# DotSolar.net
KiCad netlist of a schematic drawn in EAGLE
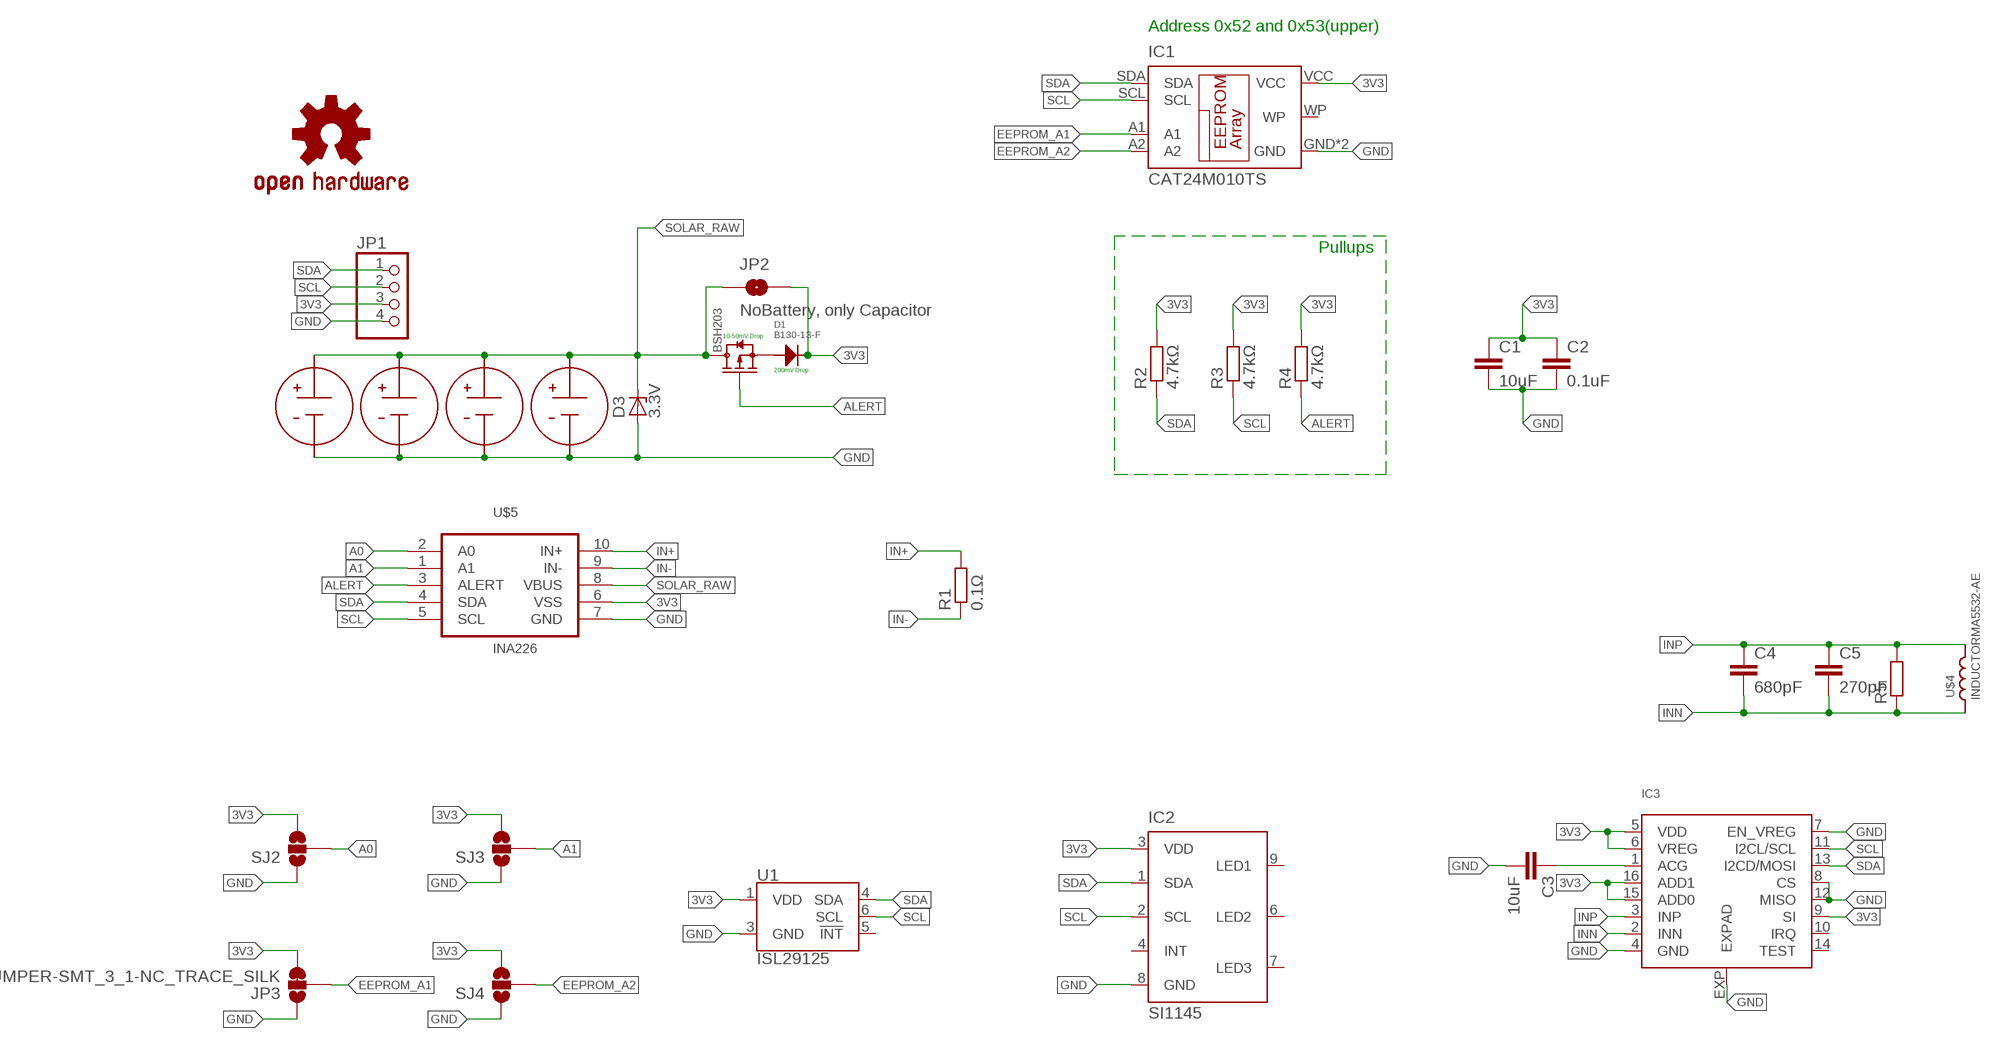
[diagram p0: schematic, sheet 1]

(export (version "E")
  (design (tool "Eeschema 10.0.6"))
  (components
    (comp (ref "C1")
      (value "10uF")
      (footprint "eagle-import:C0603")
      (libsource (lib "eagle-import") (part "C-EUC0603"))
    )
    (comp (ref "C2")
      (value "0.1uF")
      (footprint "eagle-import:C0603")
      (libsource (lib "eagle-import") (part "C-EUC0603"))
    )
    (comp (ref "C3")
      (value "10uF")
      (footprint "eagle-import:C0603")
      (libsource (lib "eagle-import") (part "C-EUC0603"))
    )
    (comp (ref "C4")
      (value "680pF")
      (footprint "eagle-import:C0603")
      (libsource (lib "eagle-import") (part "C-EUC0603"))
    )
    (comp (ref "C5")
      (value "270pF")
      (footprint "eagle-import:C0603")
      (libsource (lib "eagle-import") (part "C-EUC0603"))
    )
    (comp (ref "D1")
      (value "B130-13-F")
      (footprint "eagle-import:B130-13-F")
      (libsource (lib "eagle-import") (part "DIODE_B130-13-F"))
    )
    (comp (ref "D3")
      (value "3.3V")
      (footprint "eagle-import:SMB")
      (libsource (lib "eagle-import") (part "ZENER-DIODESMB"))
    )
    (comp (ref "IC1")
      (value "CAT24M010TS")
      (footprint "eagle-import:TSSOP8")
      (fields (field (name "MF") "On Semiconductor") (field (name "MPN") "24C00T-E/ST"))
      (libsource (lib "eagle-import") (part "CAT24M01TS0"))
    )
    (comp (ref "IC2")
      (value "SI1145")
      (footprint "eagle-import:QFN-10")
      (libsource (lib "eagle-import") (part "SI1145"))
    )
    (comp (ref "IC3")
      (value "AS3935")
      (footprint "eagle-import:16LDMLPQ")
      (libsource (lib "eagle-import") (part "AS3935"))
    )
    (comp (ref "JP1")
      (value "PINHD-1X4")
      (footprint "eagle-import:1X04")
      (libsource (lib "eagle-import") (part "PINHD-1X4"))
    )
    (comp (ref "JP2")
      (value "NoBattery, only Capacitor")
      (footprint "eagle-import:SMT-JUMPER_2_NO_SILK")
      (libsource (lib "eagle-import") (part "JUMPER-SMT_2_NO_SILK"))
    )
    (comp (ref "JP3")
      (value "JUMPER-SMT_3_1-NC_TRACE_SILK")
      (footprint "eagle-import:SMT-JUMPER_3_1-NC_TRACE_SILK")
      (libsource (lib "eagle-import") (part "JUMPER-SMT_3_1-NC_TRACE_SILK"))
    )
    (comp (ref "LOGO1")
      (value "OSHW-LOGOS")
      (footprint "eagle-import:OSHW-LOGO-S")
      (libsource (lib "eagle-import") (part "OSHW-LOGOS"))
    )
    (comp (ref "Q1")
      (value "BSH203")
      (footprint "eagle-import:SOT-23")
      (libsource (lib "eagle-import") (part "BSH203"))
    )
    (comp (ref "R1")
      (value "0.1Ω")
      (footprint "eagle-import:R0603")
      (libsource (lib "eagle-import") (part "R-EU_R0603"))
    )
    (comp (ref "R2")
      (value "4.7kΩ")
      (footprint "eagle-import:R0603")
      (libsource (lib "eagle-import") (part "R-EU_R0603"))
    )
    (comp (ref "R3")
      (value "4.7kΩ")
      (footprint "eagle-import:R0603")
      (libsource (lib "eagle-import") (part "R-EU_R0603"))
    )
    (comp (ref "R4")
      (value "4.7kΩ")
      (footprint "eagle-import:R0603")
      (libsource (lib "eagle-import") (part "R-EU_R0603"))
    )
    (comp (ref "R5")
      (value "R-EU_R0603")
      (footprint "eagle-import:R0603")
      (libsource (lib "eagle-import") (part "R-EU_R0603"))
    )
    (comp (ref "SJ2")
      (value "SOLDERJUMPER_2WAYPASTE2&3")
      (footprint "eagle-import:SJ_3_PASTE2&3")
      (libsource (lib "eagle-import") (part "SOLDERJUMPER_2WAYPASTE2&3"))
    )
    (comp (ref "SJ3")
      (value "SOLDERJUMPER_2WAYPASTE2&3")
      (footprint "eagle-import:SJ_3_PASTE2&3")
      (libsource (lib "eagle-import") (part "SOLDERJUMPER_2WAYPASTE2&3"))
    )
    (comp (ref "SJ4")
      (value "SOLDERJUMPER_2WAYPASTE2&3")
      (footprint "eagle-import:SJ_3_PASTE2&3")
      (libsource (lib "eagle-import") (part "SOLDERJUMPER_2WAYPASTE2&3"))
    )
    (comp (ref "U$1")
      (value "KXOB22-01X8F_EXTENDED_PADS")
      (footprint "eagle-import:KXOB22-01X8F_EXTENDED_PADS")
      (libsource (lib "eagle-import") (part "KXOB22-01X8F_EXTENDED_PADS"))
    )
    (comp (ref "U$2")
      (value "KXOB22-01X8F_EXTENDED_PADS")
      (footprint "eagle-import:KXOB22-01X8F_EXTENDED_PADS")
      (libsource (lib "eagle-import") (part "KXOB22-01X8F_EXTENDED_PADS"))
    )
    (comp (ref "U$3")
      (value "KXOB22-01X8F_EXTENDED_PADS")
      (footprint "eagle-import:KXOB22-01X8F_EXTENDED_PADS")
      (libsource (lib "eagle-import") (part "KXOB22-01X8F_EXTENDED_PADS"))
    )
    (comp (ref "U$4")
      (value "INDUCTORMA5532-AE")
      (footprint "eagle-import:MA5532-AE")
      (libsource (lib "eagle-import") (part "INDUCTORMA5532-AE"))
    )
    (comp (ref "U$5")
      (value "INA226")
      (footprint "eagle-import:VSSOP-10")
      (libsource (lib "eagle-import") (part "INA226"))
    )
    (comp (ref "U$6")
      (value "KXOB22-01X8F_EXTENDED_PADS")
      (footprint "eagle-import:KXOB22-01X8F_EXTENDED_PADS")
      (libsource (lib "eagle-import") (part "KXOB22-01X8F_EXTENDED_PADS"))
    )
    (comp (ref "U1")
      (value "ISL29125")
      (footprint "eagle-import:ODFN-6")
      (libsource (lib "eagle-import") (part "ISL29125"))
    )
  )
  (nets
    (net (code "1") (name "3V3") (class "Default")
      (node (ref "C1") (pin "1") (pinfunction "1_1") (pintype "passive"))
      (node (ref "C2") (pin "1") (pinfunction "1_1") (pintype "passive"))
      (node (ref "D1") (pin "CATHODE") (pinfunction "CATHODE_CATHODE") (pintype "bidirectional"))
      (node (ref "IC1") (pin "VCC") (pinfunction "VCC_VCC") (pintype "power_in"))
      (node (ref "IC2") (pin "3") (pinfunction "VDD_3") (pintype "power_in"))
      (node (ref "IC3") (pin "15") (pinfunction "ADD0_15") (pintype "bidirectional"))
      (node (ref "IC3") (pin "16") (pinfunction "ADD1_16") (pintype "bidirectional"))
      (node (ref "IC3") (pin "5") (pinfunction "VDD_5") (pintype "power_in"))
      (node (ref "IC3") (pin "6") (pinfunction "VREG_6") (pintype "bidirectional"))
      (node (ref "IC3") (pin "9") (pinfunction "SI_9") (pintype "bidirectional"))
      (node (ref "JP1") (pin "3") (pinfunction "3_3") (pintype "passive"))
      (node (ref "JP2") (pin "2") (pinfunction "2_2") (pintype "passive"))
      (node (ref "JP3") (pin "3") (pinfunction "3_3") (pintype "passive"))
      (node (ref "R2") (pin "2") (pinfunction "2_2") (pintype "passive"))
      (node (ref "R3") (pin "2") (pinfunction "2_2") (pintype "passive"))
      (node (ref "R4") (pin "2") (pinfunction "2_2") (pintype "passive"))
      (node (ref "SJ2") (pin "3") (pinfunction "3_3") (pintype "passive"))
      (node (ref "SJ3") (pin "3") (pinfunction "3_3") (pintype "passive"))
      (node (ref "SJ4") (pin "3") (pinfunction "3_3") (pintype "passive"))
      (node (ref "U$5") (pin "6") (pinfunction "VSS_6") (pintype "power_in"))
      (node (ref "U1") (pin "1") (pinfunction "VDD_1") (pintype "bidirectional"))
    )
    (net (code "2") (name "A0") (class "Default")
      (node (ref "SJ2") (pin "2") (pinfunction "2_2") (pintype "passive"))
      (node (ref "U$5") (pin "2") (pinfunction "A0_2") (pintype "input"))
    )
    (net (code "3") (name "A1") (class "Default")
      (node (ref "SJ3") (pin "2") (pinfunction "2_2") (pintype "passive"))
      (node (ref "U$5") (pin "1") (pinfunction "A1_1") (pintype "input"))
    )
    (net (code "4") (name "ALERT") (class "Default")
      (node (ref "Q1") (pin "1") (pinfunction "G_1") (pintype "passive"))
      (node (ref "R4") (pin "1") (pinfunction "1_1") (pintype "passive"))
      (node (ref "U$5") (pin "3") (pinfunction "ALERT_3") (pintype "input"))
    )
    (net (code "5") (name "EEPROM_A1") (class "Default")
      (node (ref "IC1") (pin "A1") (pinfunction "A1_A1") (pintype "bidirectional"))
      (node (ref "JP3") (pin "2") (pinfunction "2_2") (pintype "passive"))
    )
    (net (code "6") (name "EEPROM_A2") (class "Default")
      (node (ref "IC1") (pin "A2") (pinfunction "A2_A2") (pintype "bidirectional"))
      (node (ref "SJ4") (pin "2") (pinfunction "2_2") (pintype "passive"))
    )
    (net (code "7") (name "GND") (class "Default")
      (node (ref "C1") (pin "2") (pinfunction "2_2") (pintype "passive"))
      (node (ref "C2") (pin "2") (pinfunction "2_2") (pintype "passive"))
      (node (ref "C3") (pin "2") (pinfunction "2_2") (pintype "passive"))
      (node (ref "D3") (pin "A") (pinfunction "A_A") (pintype "passive"))
      (node (ref "IC1") (pin "GND") (pinfunction "GND_GND") (pintype "power_in"))
      (node (ref "IC1") (pin "NC") (pinfunction "GND_NC") (pintype "power_in"))
      (node (ref "IC2") (pin "8") (pinfunction "GND_8") (pintype "power_in"))
      (node (ref "IC3") (pin "12") (pinfunction "MISO_12") (pintype "bidirectional"))
      (node (ref "IC3") (pin "4") (pinfunction "GND_4") (pintype "power_in"))
      (node (ref "IC3") (pin "7") (pinfunction "EN_VREG_7") (pintype "bidirectional"))
      (node (ref "IC3") (pin "8") (pinfunction "CS_8") (pintype "bidirectional"))
      (node (ref "IC3") (pin "EXP") (pinfunction "EXPAD_EXP") (pintype "power_in"))
      (node (ref "JP1") (pin "4") (pinfunction "4_4") (pintype "passive"))
      (node (ref "JP3") (pin "1") (pinfunction "1_1") (pintype "passive"))
      (node (ref "SJ2") (pin "1") (pinfunction "1_1") (pintype "passive"))
      (node (ref "SJ3") (pin "1") (pinfunction "1_1") (pintype "passive"))
      (node (ref "SJ4") (pin "1") (pinfunction "1_1") (pintype "passive"))
      (node (ref "U$1") (pin "P$1") (pinfunction "P$1_P$1") (pintype "power_in"))
      (node (ref "U$2") (pin "P$1") (pinfunction "P$1_P$1") (pintype "power_in"))
      (node (ref "U$3") (pin "P$1") (pinfunction "P$1_P$1") (pintype "power_in"))
      (node (ref "U$5") (pin "7") (pinfunction "GND_7") (pintype "power_in"))
      (node (ref "U$6") (pin "P$1") (pinfunction "P$1_P$1") (pintype "power_in"))
      (node (ref "U1") (pin "3") (pinfunction "GND_3") (pintype "bidirectional"))
    )
    (net (code "8") (name "IN+") (class "Default")
      (node (ref "R1") (pin "2") (pinfunction "2_2") (pintype "passive"))
      (node (ref "U$5") (pin "10") (pinfunction "IN+_10") (pintype "input"))
    )
    (net (code "9") (name "IN-") (class "Default")
      (node (ref "R1") (pin "1") (pinfunction "1_1") (pintype "passive"))
      (node (ref "U$5") (pin "9") (pinfunction "IN-_9") (pintype "input"))
    )
    (net (code "10") (name "INN") (class "Default")
      (node (ref "C4") (pin "2") (pinfunction "2_2") (pintype "passive"))
      (node (ref "C5") (pin "2") (pinfunction "2_2") (pintype "passive"))
      (node (ref "IC3") (pin "2") (pinfunction "INN_2") (pintype "bidirectional"))
      (node (ref "R5") (pin "1") (pinfunction "1_1") (pintype "passive"))
      (node (ref "U$4") (pin "2") (pinfunction "2_2") (pintype "bidirectional"))
    )
    (net (code "11") (name "INP") (class "Default")
      (node (ref "C4") (pin "1") (pinfunction "1_1") (pintype "passive"))
      (node (ref "C5") (pin "1") (pinfunction "1_1") (pintype "passive"))
      (node (ref "IC3") (pin "3") (pinfunction "INP_3") (pintype "bidirectional"))
      (node (ref "R5") (pin "2") (pinfunction "2_2") (pintype "passive"))
      (node (ref "U$4") (pin "1") (pinfunction "1_1") (pintype "bidirectional"))
    )
    (net (code "12") (name "Net-(IC3-ACG)") (class "Default")
      (node (ref "C3") (pin "1") (pinfunction "1_1") (pintype "passive"))
      (node (ref "IC3") (pin "1") (pinfunction "ACG_1") (pintype "bidirectional"))
    )
    (net (code "13") (name "Net-(Q1-S)") (class "Default")
      (node (ref "D1") (pin "ANODE") (pinfunction "ANODE_ANODE") (pintype "bidirectional"))
      (node (ref "Q1") (pin "2") (pinfunction "S_2") (pintype "passive"))
    )
    (net (code "14") (name "SCL") (class "Default")
      (node (ref "IC1") (pin "SCL") (pinfunction "SCL_SCL") (pintype "input"))
      (node (ref "IC2") (pin "2") (pinfunction "SCL_2") (pintype "input"))
      (node (ref "IC3") (pin "11") (pinfunction "I2CL/SCL_11") (pintype "bidirectional"))
      (node (ref "JP1") (pin "2") (pinfunction "2_2") (pintype "passive"))
      (node (ref "R3") (pin "1") (pinfunction "1_1") (pintype "passive"))
      (node (ref "U$5") (pin "5") (pinfunction "SCL_5") (pintype "input"))
      (node (ref "U1") (pin "6") (pinfunction "SCL_6") (pintype "bidirectional"))
    )
    (net (code "15") (name "SDA") (class "Default")
      (node (ref "IC1") (pin "SDA") (pinfunction "SDA_SDA") (pintype "bidirectional"))
      (node (ref "IC2") (pin "1") (pinfunction "SDA_1") (pintype "bidirectional"))
      (node (ref "IC3") (pin "13") (pinfunction "I2CD/MOSI_13") (pintype "bidirectional"))
      (node (ref "JP1") (pin "1") (pinfunction "1_1") (pintype "passive"))
      (node (ref "R2") (pin "1") (pinfunction "1_1") (pintype "passive"))
      (node (ref "U$5") (pin "4") (pinfunction "SDA_4") (pintype "input"))
      (node (ref "U1") (pin "4") (pinfunction "SDA_4") (pintype "bidirectional"))
    )
    (net (code "16") (name "SOLAR_RAW") (class "Default")
      (node (ref "D3") (pin "C") (pinfunction "C_C") (pintype "passive"))
      (node (ref "JP2") (pin "1") (pinfunction "1_1") (pintype "passive"))
      (node (ref "Q1") (pin "3") (pinfunction "D_3") (pintype "passive"))
      (node (ref "U$1") (pin "P$2") (pinfunction "P$2_P$2") (pintype "power_in"))
      (node (ref "U$2") (pin "P$2") (pinfunction "P$2_P$2") (pintype "power_in"))
      (node (ref "U$3") (pin "P$2") (pinfunction "P$2_P$2") (pintype "power_in"))
      (node (ref "U$5") (pin "8") (pinfunction "VBUS_8") (pintype "passive"))
      (node (ref "U$6") (pin "P$2") (pinfunction "P$2_P$2") (pintype "power_in"))
    )
    (net (code "17") (name "unconnected-(IC1-PadWP)") (class "Default")
      (node (ref "IC1") (pin "WP") (pinfunction "WP_WP") (pintype "bidirectional"))
    )
    (net (code "18") (name "unconnected-(IC2-INT-Pad4)") (class "Default")
      (node (ref "IC2") (pin "4") (pinfunction "INT_4") (pintype "open_collector"))
    )
    (net (code "19") (name "unconnected-(IC2-LED1-Pad9)") (class "Default")
      (node (ref "IC2") (pin "9") (pinfunction "LED1_9") (pintype "output"))
    )
    (net (code "20") (name "unconnected-(IC2-LED2-Pad6)") (class "Default")
      (node (ref "IC2") (pin "6") (pinfunction "LED2_6") (pintype "output"))
    )
    (net (code "21") (name "unconnected-(IC2-LED3-Pad7)") (class "Default")
      (node (ref "IC2") (pin "7") (pinfunction "LED3_7") (pintype "output"))
    )
    (net (code "22") (name "unconnected-(IC3-IRQ-Pad10)") (class "Default")
      (node (ref "IC3") (pin "10") (pinfunction "IRQ_10") (pintype "bidirectional"))
    )
    (net (code "23") (name "unconnected-(IC3-TEST-Pad14)") (class "Default")
      (node (ref "IC3") (pin "14") (pinfunction "TEST_14") (pintype "passive"))
    )
    (net (code "24") (name "unconnected-(U1-~{INT}-Pad5)") (class "Default")
      (node (ref "U1") (pin "5") (pinfunction "~{INT}_5") (pintype "bidirectional"))
    )
  )
)
